# snullv2.net
KiCad netlist of a schematic drawn in EAGLE
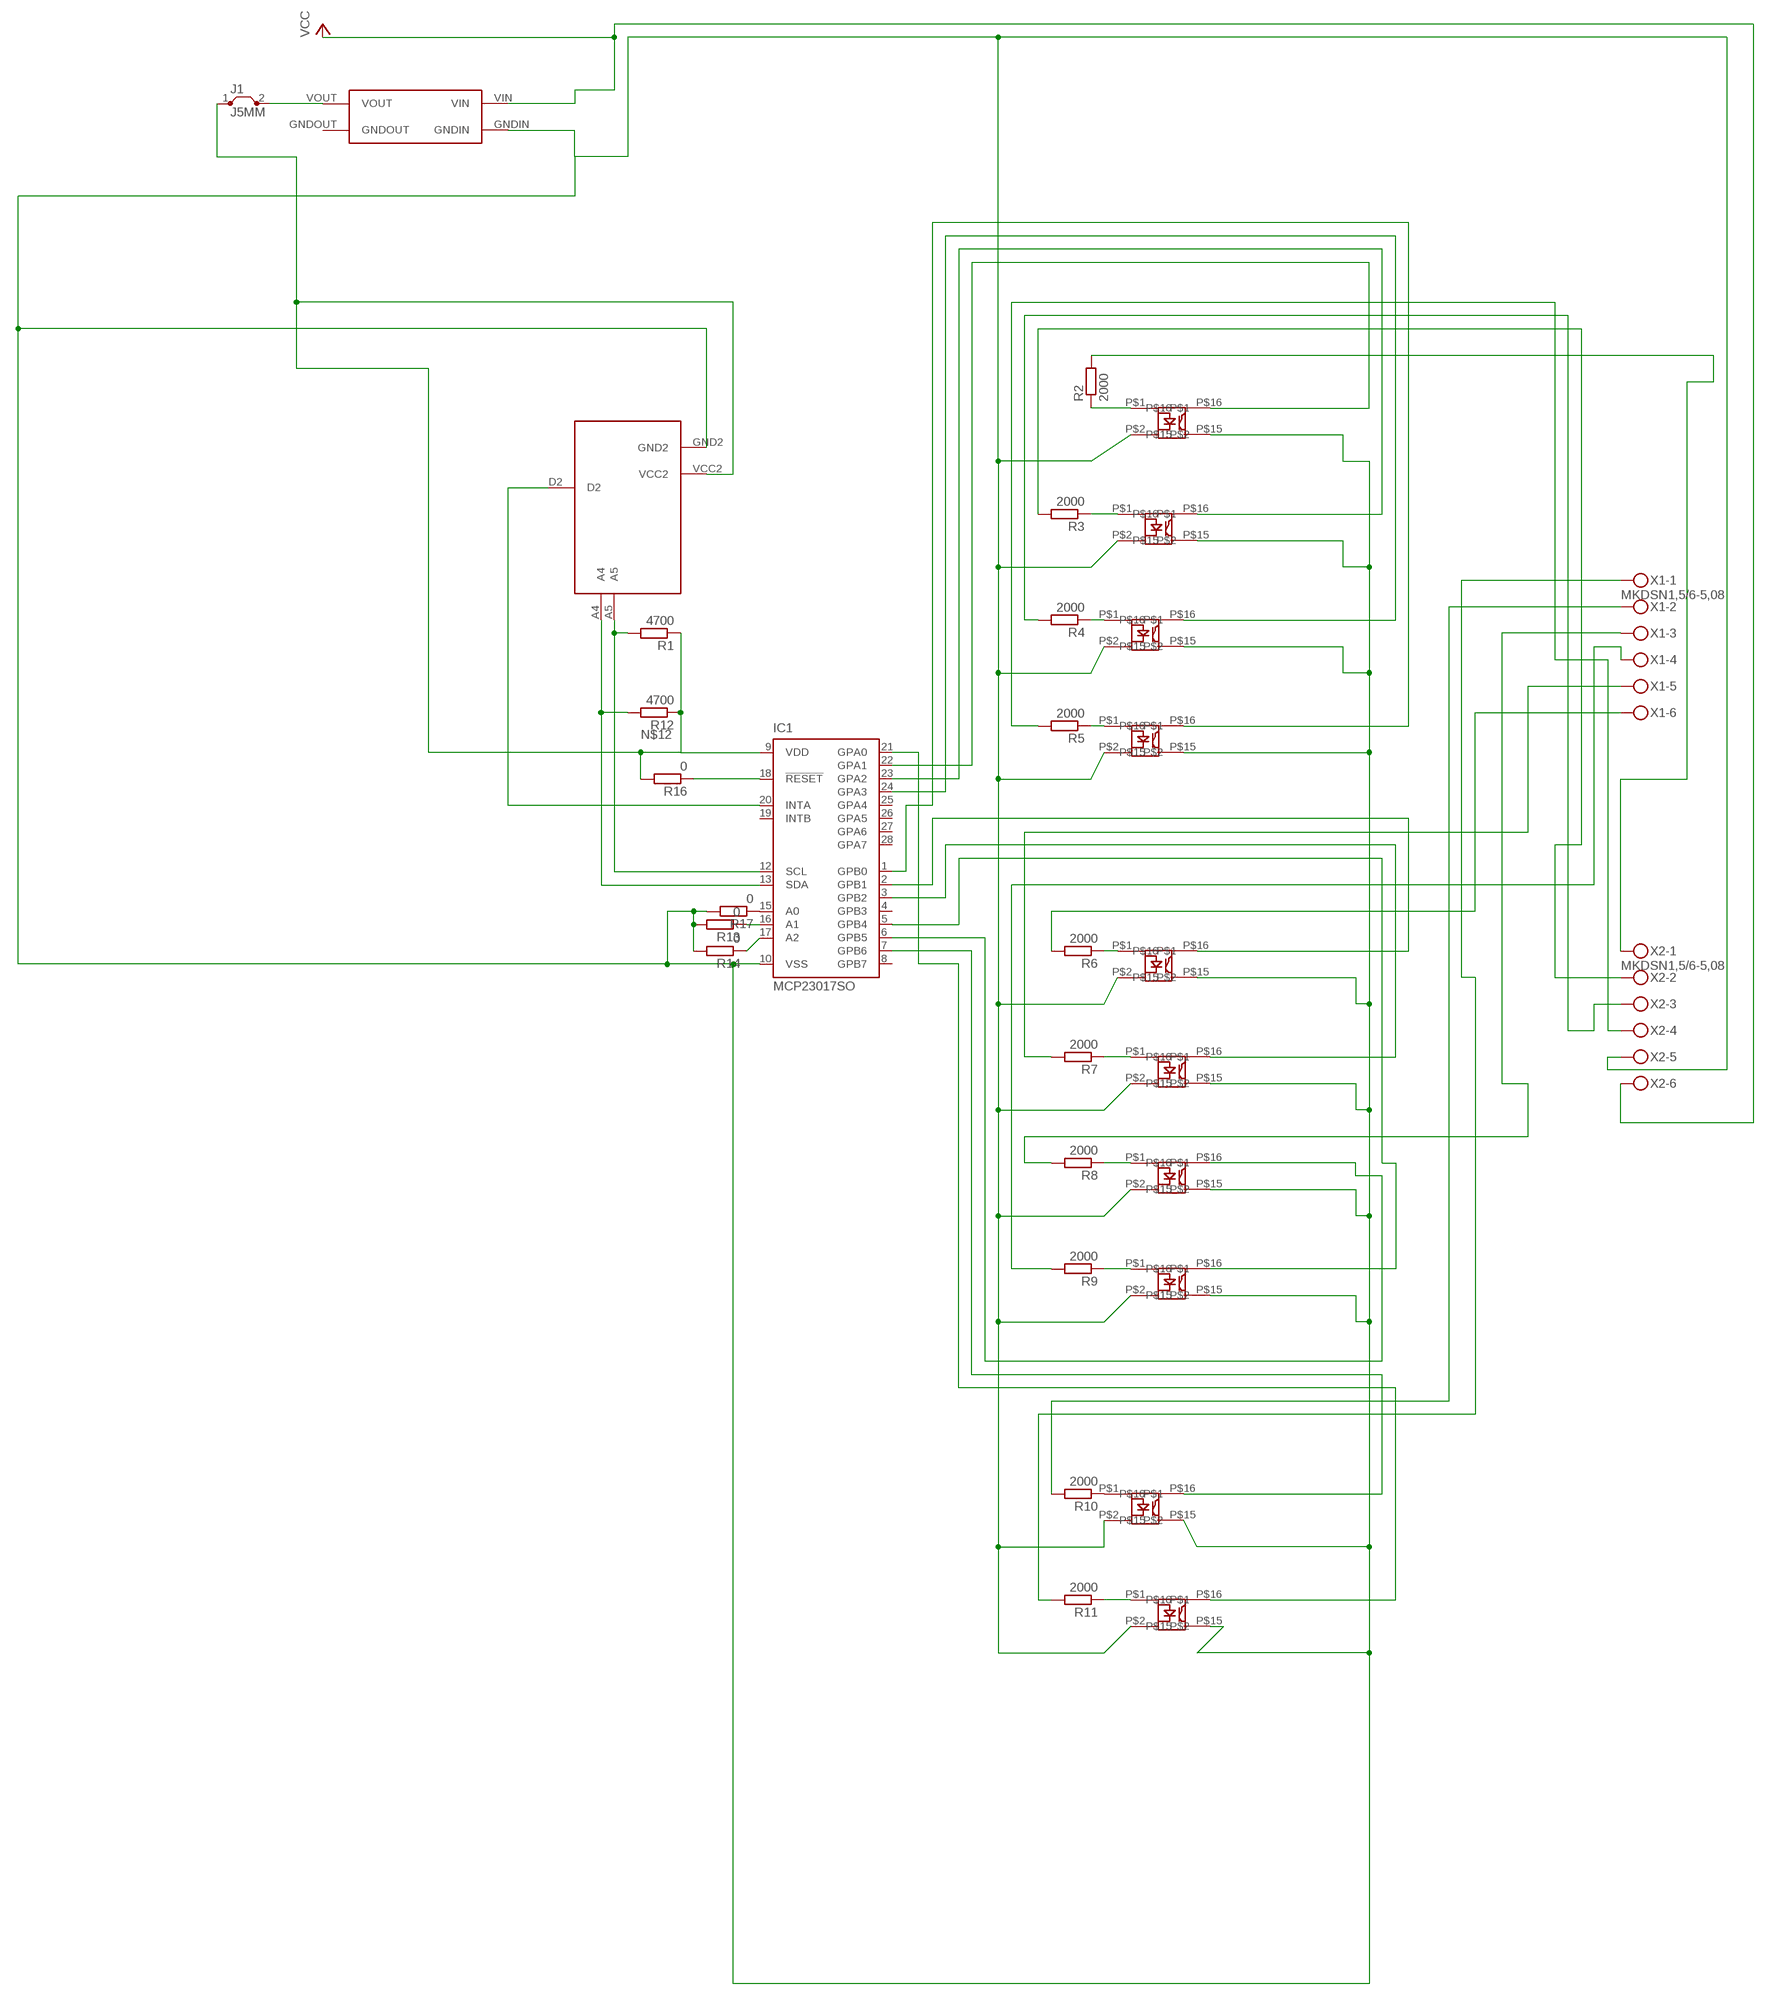
[diagram p0: schematic, sheet 1]

(export (version "E")
  (design (tool "Eeschema 10.0.6"))
  (components
    (comp (ref "IC1")
      (value "MCP23017SO")
      (footprint "eagle-import:SO28W")
      (fields (field (name "MF") "MICROCHIP") (field (name "MPN") "MCP23017-E/SO"))
      (libsource (lib "eagle-import") (part "MCP23017SO"))
    )
    (comp (ref "J1")
      (value "J5MM")
      (footprint "eagle-import:05")
      (libsource (lib "eagle-import") (part "J5MM"))
    )
    (comp (ref "R1")
      (value "4700")
      (footprint "eagle-import:R0805")
      (libsource (lib "eagle-import") (part "R-EU_R0805"))
    )
    (comp (ref "R2")
      (value "2000")
      (footprint "eagle-import:R0805")
      (libsource (lib "eagle-import") (part "R-EU_R0805"))
    )
    (comp (ref "R3")
      (value "2000")
      (footprint "eagle-import:R0805")
      (libsource (lib "eagle-import") (part "R-EU_R0805"))
    )
    (comp (ref "R4")
      (value "2000")
      (footprint "eagle-import:R0805")
      (libsource (lib "eagle-import") (part "R-EU_R0805"))
    )
    (comp (ref "R5")
      (value "2000")
      (footprint "eagle-import:R0805")
      (libsource (lib "eagle-import") (part "R-EU_R0805"))
    )
    (comp (ref "R6")
      (value "2000")
      (footprint "eagle-import:R0805")
      (libsource (lib "eagle-import") (part "R-EU_R0805"))
    )
    (comp (ref "R7")
      (value "2000")
      (footprint "eagle-import:R0805")
      (libsource (lib "eagle-import") (part "R-EU_R0805"))
    )
    (comp (ref "R8")
      (value "2000")
      (footprint "eagle-import:R0805")
      (libsource (lib "eagle-import") (part "R-EU_R0805"))
    )
    (comp (ref "R9")
      (value "2000")
      (footprint "eagle-import:R0805")
      (libsource (lib "eagle-import") (part "R-EU_R0805"))
    )
    (comp (ref "R10")
      (value "2000")
      (footprint "eagle-import:R0805")
      (libsource (lib "eagle-import") (part "R-EU_R0805"))
    )
    (comp (ref "R11")
      (value "2000")
      (footprint "eagle-import:R0805")
      (libsource (lib "eagle-import") (part "R-EU_R0805"))
    )
    (comp (ref "R12")
      (value "4700")
      (footprint "eagle-import:R0805")
      (libsource (lib "eagle-import") (part "R-EU_R0805"))
    )
    (comp (ref "R13")
      (value "0")
      (footprint "eagle-import:R0805")
      (libsource (lib "eagle-import") (part "R-EU_R0805"))
    )
    (comp (ref "R14")
      (value "0")
      (footprint "eagle-import:R0805")
      (libsource (lib "eagle-import") (part "R-EU_R0805"))
    )
    (comp (ref "R16")
      (value "0")
      (footprint "eagle-import:R0805")
      (libsource (lib "eagle-import") (part "R-EU_R0805"))
    )
    (comp (ref "R17")
      (value "0")
      (footprint "eagle-import:R0805")
      (libsource (lib "eagle-import") (part "R-EU_R0805"))
    )
    (comp (ref "U$1")
      (value "ARDUINOPROMINIREDUCED")
      (footprint "eagle-import:ARDUINOPROMINIREDUCED")
      (libsource (lib "eagle-import") (part "ARDUINOPROMINIREDUCED"))
    )
    (comp (ref "U$3")
      (value "OPTO1CHAN")
      (footprint "eagle-import:OPTO1CHAN")
      (libsource (lib "eagle-import") (part "OPTO1CHAN"))
    )
    (comp (ref "U$4")
      (value "OPTO1CHAN")
      (footprint "eagle-import:OPTO1CHAN")
      (libsource (lib "eagle-import") (part "OPTO1CHAN"))
    )
    (comp (ref "U$5")
      (value "VREGMODULE")
      (footprint "eagle-import:VREGMODULE")
      (libsource (lib "eagle-import") (part "VREGMODULE"))
    )
    (comp (ref "U$6")
      (value "OPTO1CHAN")
      (footprint "eagle-import:OPTO1CHAN")
      (libsource (lib "eagle-import") (part "OPTO1CHAN"))
    )
    (comp (ref "U$7")
      (value "OPTO1CHAN")
      (footprint "eagle-import:OPTO1CHAN")
      (libsource (lib "eagle-import") (part "OPTO1CHAN"))
    )
    (comp (ref "U$8")
      (value "OPTO1CHAN")
      (footprint "eagle-import:OPTO1CHAN")
      (libsource (lib "eagle-import") (part "OPTO1CHAN"))
    )
    (comp (ref "U$9")
      (value "OPTO1CHAN")
      (footprint "eagle-import:OPTO1CHAN")
      (libsource (lib "eagle-import") (part "OPTO1CHAN"))
    )
    (comp (ref "U$10")
      (value "OPTO1CHAN")
      (footprint "eagle-import:OPTO1CHAN")
      (libsource (lib "eagle-import") (part "OPTO1CHAN"))
    )
    (comp (ref "U$11")
      (value "OPTO1CHAN")
      (footprint "eagle-import:OPTO1CHAN")
      (libsource (lib "eagle-import") (part "OPTO1CHAN"))
    )
    (comp (ref "U$12")
      (value "OPTO1CHAN")
      (footprint "eagle-import:OPTO1CHAN")
      (libsource (lib "eagle-import") (part "OPTO1CHAN"))
    )
    (comp (ref "U$13")
      (value "OPTO1CHAN")
      (footprint "eagle-import:OPTO1CHAN")
      (libsource (lib "eagle-import") (part "OPTO1CHAN"))
    )
    (comp (ref "X1")
      (value "MKDSN1,5/6-5,08")
      (footprint "eagle-import:MKDSN1,5_6-5,08")
      (libsource (lib "eagle-import") (part "MKDSN1,5/6-5,08"))
    )
    (comp (ref "X2")
      (value "MKDSN1,5/6-5,08")
      (footprint "eagle-import:MKDSN1,5_6-5,08")
      (libsource (lib "eagle-import") (part "MKDSN1,5/6-5,08"))
    )
  )
  (nets
    (net (code "1") (name "/N$12") (class "Default")
      (node (ref "IC1") (pin "9") (pinfunction "VDD_9") (pintype "power_in"))
      (node (ref "J1") (pin "1") (pinfunction "1_1") (pintype "passive"))
      (node (ref "R1") (pin "1") (pinfunction "1_1") (pintype "passive"))
      (node (ref "R12") (pin "1") (pinfunction "1_1") (pintype "passive"))
      (node (ref "R16") (pin "2") (pinfunction "2_2") (pintype "passive"))
      (node (ref "U$1") (pin "VCC2") (pinfunction "VCC2_VCC2") (pintype "bidirectional"))
    )
    (net (code "2") (name "Net-(IC1-A0)") (class "Default")
      (node (ref "IC1") (pin "15") (pinfunction "A0_15") (pintype "input"))
      (node (ref "R17") (pin "1") (pinfunction "1_1") (pintype "passive"))
    )
    (net (code "3") (name "Net-(IC1-A1)") (class "Default")
      (node (ref "IC1") (pin "16") (pinfunction "A1_16") (pintype "input"))
      (node (ref "R13") (pin "1") (pinfunction "1_1") (pintype "passive"))
    )
    (net (code "4") (name "Net-(IC1-A2)") (class "Default")
      (node (ref "IC1") (pin "17") (pinfunction "A2_17") (pintype "input"))
      (node (ref "R14") (pin "1") (pinfunction "1_1") (pintype "passive"))
    )
    (net (code "5") (name "Net-(IC1-GPA0)") (class "Default")
      (node (ref "IC1") (pin "21") (pinfunction "GPA0_21") (pintype "bidirectional"))
      (node (ref "U$13") (pin "P$16") (pinfunction "P$16_P$16") (pintype "bidirectional"))
    )
    (net (code "6") (name "Net-(IC1-GPA1)") (class "Default")
      (node (ref "IC1") (pin "22") (pinfunction "GPA1_22") (pintype "bidirectional"))
      (node (ref "U$3") (pin "P$16") (pinfunction "P$16_P$16") (pintype "bidirectional"))
    )
    (net (code "7") (name "Net-(IC1-GPA2)") (class "Default")
      (node (ref "IC1") (pin "23") (pinfunction "GPA2_23") (pintype "bidirectional"))
      (node (ref "U$4") (pin "P$16") (pinfunction "P$16_P$16") (pintype "bidirectional"))
    )
    (net (code "8") (name "Net-(IC1-GPA3)") (class "Default")
      (node (ref "IC1") (pin "24") (pinfunction "GPA3_24") (pintype "bidirectional"))
      (node (ref "U$6") (pin "P$16") (pinfunction "P$16_P$16") (pintype "bidirectional"))
    )
    (net (code "9") (name "Net-(IC1-GPB0)") (class "Default")
      (node (ref "IC1") (pin "1") (pinfunction "GPB0_1") (pintype "bidirectional"))
      (node (ref "U$7") (pin "P$16") (pinfunction "P$16_P$16") (pintype "bidirectional"))
    )
    (net (code "10") (name "Net-(IC1-GPB1)") (class "Default")
      (node (ref "IC1") (pin "2") (pinfunction "GPB1_2") (pintype "bidirectional"))
      (node (ref "U$8") (pin "P$16") (pinfunction "P$16_P$16") (pintype "bidirectional"))
    )
    (net (code "11") (name "Net-(IC1-GPB2)") (class "Default")
      (node (ref "IC1") (pin "3") (pinfunction "GPB2_3") (pintype "bidirectional"))
      (node (ref "U$9") (pin "P$16") (pinfunction "P$16_P$16") (pintype "bidirectional"))
    )
    (net (code "12") (name "Net-(IC1-GPB4)") (class "Default")
      (node (ref "IC1") (pin "5") (pinfunction "GPB4_5") (pintype "bidirectional"))
      (node (ref "U$11") (pin "P$16") (pinfunction "P$16_P$16") (pintype "bidirectional"))
    )
    (net (code "13") (name "Net-(IC1-GPB5)") (class "Default")
      (node (ref "IC1") (pin "6") (pinfunction "GPB5_6") (pintype "bidirectional"))
      (node (ref "U$10") (pin "P$16") (pinfunction "P$16_P$16") (pintype "bidirectional"))
    )
    (net (code "14") (name "Net-(IC1-GPB6)") (class "Default")
      (node (ref "IC1") (pin "7") (pinfunction "GPB6_7") (pintype "bidirectional"))
      (node (ref "U$12") (pin "P$16") (pinfunction "P$16_P$16") (pintype "bidirectional"))
    )
    (net (code "15") (name "Net-(IC1-INTA)") (class "Default")
      (node (ref "IC1") (pin "20") (pinfunction "INTA_20") (pintype "output"))
      (node (ref "U$1") (pin "D2") (pinfunction "D2_D2") (pintype "bidirectional"))
    )
    (net (code "16") (name "Net-(IC1-SCL)") (class "Default")
      (node (ref "IC1") (pin "12") (pinfunction "SCL_12") (pintype "input"))
      (node (ref "R1") (pin "2") (pinfunction "2_2") (pintype "passive"))
      (node (ref "U$1") (pin "A5") (pinfunction "A5_A5") (pintype "bidirectional"))
    )
    (net (code "17") (name "Net-(IC1-SDA)") (class "Default")
      (node (ref "IC1") (pin "13") (pinfunction "SDA_13") (pintype "bidirectional"))
      (node (ref "R12") (pin "2") (pinfunction "2_2") (pintype "passive"))
      (node (ref "U$1") (pin "A4") (pinfunction "A4_A4") (pintype "bidirectional"))
    )
    (net (code "18") (name "Net-(IC1-VSS)") (class "Default")
      (node (ref "IC1") (pin "10") (pinfunction "VSS_10") (pintype "power_in"))
      (node (ref "R13") (pin "2") (pinfunction "2_2") (pintype "passive"))
      (node (ref "R14") (pin "2") (pinfunction "2_2") (pintype "passive"))
      (node (ref "R17") (pin "2") (pinfunction "2_2") (pintype "passive"))
      (node (ref "U$1") (pin "GND2") (pinfunction "GND2_GND2") (pintype "bidirectional"))
      (node (ref "U$10") (pin "P$15") (pinfunction "P$15_P$15") (pintype "bidirectional"))
      (node (ref "U$10") (pin "P$2") (pinfunction "P$2_P$2") (pintype "bidirectional"))
      (node (ref "U$11") (pin "P$15") (pinfunction "P$15_P$15") (pintype "bidirectional"))
      (node (ref "U$11") (pin "P$2") (pinfunction "P$2_P$2") (pintype "bidirectional"))
      (node (ref "U$12") (pin "P$15") (pinfunction "P$15_P$15") (pintype "bidirectional"))
      (node (ref "U$12") (pin "P$2") (pinfunction "P$2_P$2") (pintype "bidirectional"))
      (node (ref "U$13") (pin "P$15") (pinfunction "P$15_P$15") (pintype "bidirectional"))
      (node (ref "U$13") (pin "P$2") (pinfunction "P$2_P$2") (pintype "bidirectional"))
      (node (ref "U$3") (pin "P$15") (pinfunction "P$15_P$15") (pintype "bidirectional"))
      (node (ref "U$3") (pin "P$2") (pinfunction "P$2_P$2") (pintype "bidirectional"))
      (node (ref "U$4") (pin "P$15") (pinfunction "P$15_P$15") (pintype "bidirectional"))
      (node (ref "U$4") (pin "P$2") (pinfunction "P$2_P$2") (pintype "bidirectional"))
      (node (ref "U$5") (pin "GNDIN") (pinfunction "GNDIN_GNDIN") (pintype "bidirectional"))
      (node (ref "U$6") (pin "P$15") (pinfunction "P$15_P$15") (pintype "bidirectional"))
      (node (ref "U$6") (pin "P$2") (pinfunction "P$2_P$2") (pintype "bidirectional"))
      (node (ref "U$7") (pin "P$15") (pinfunction "P$15_P$15") (pintype "bidirectional"))
      (node (ref "U$7") (pin "P$2") (pinfunction "P$2_P$2") (pintype "bidirectional"))
      (node (ref "U$8") (pin "P$15") (pinfunction "P$15_P$15") (pintype "bidirectional"))
      (node (ref "U$8") (pin "P$2") (pinfunction "P$2_P$2") (pintype "bidirectional"))
      (node (ref "U$9") (pin "P$15") (pinfunction "P$15_P$15") (pintype "bidirectional"))
      (node (ref "U$9") (pin "P$2") (pinfunction "P$2_P$2") (pintype "bidirectional"))
      (node (ref "X2") (pin "5") (pinfunction "KL_5") (pintype "passive"))
    )
    (net (code "19") (name "Net-(IC1-~{RESET})") (class "Default")
      (node (ref "IC1") (pin "18") (pinfunction "~{RESET}_18") (pintype "input"))
      (node (ref "R16") (pin "1") (pinfunction "1_1") (pintype "passive"))
    )
    (net (code "20") (name "Net-(J1-Pad2)") (class "Default")
      (node (ref "J1") (pin "2") (pinfunction "2_2") (pintype "passive"))
      (node (ref "U$5") (pin "VOUT") (pinfunction "VOUT_VOUT") (pintype "bidirectional"))
    )
    (net (code "21") (name "Net-(R2-Pad1)") (class "Default")
      (node (ref "R2") (pin "1") (pinfunction "1_1") (pintype "passive"))
      (node (ref "U$3") (pin "P$1") (pinfunction "P$1_P$1") (pintype "bidirectional"))
    )
    (net (code "22") (name "Net-(R3-Pad1)") (class "Default")
      (node (ref "R3") (pin "1") (pinfunction "1_1") (pintype "passive"))
      (node (ref "U$4") (pin "P$1") (pinfunction "P$1_P$1") (pintype "bidirectional"))
    )
    (net (code "23") (name "Net-(R4-Pad1)") (class "Default")
      (node (ref "R4") (pin "1") (pinfunction "1_1") (pintype "passive"))
      (node (ref "U$6") (pin "P$1") (pinfunction "P$1_P$1") (pintype "bidirectional"))
    )
    (net (code "24") (name "Net-(R5-Pad1)") (class "Default")
      (node (ref "R5") (pin "1") (pinfunction "1_1") (pintype "passive"))
      (node (ref "U$7") (pin "P$1") (pinfunction "P$1_P$1") (pintype "bidirectional"))
    )
    (net (code "25") (name "Net-(R6-Pad1)") (class "Default")
      (node (ref "R6") (pin "1") (pinfunction "1_1") (pintype "passive"))
      (node (ref "U$8") (pin "P$1") (pinfunction "P$1_P$1") (pintype "bidirectional"))
    )
    (net (code "26") (name "Net-(R7-Pad1)") (class "Default")
      (node (ref "R7") (pin "1") (pinfunction "1_1") (pintype "passive"))
      (node (ref "U$9") (pin "P$1") (pinfunction "P$1_P$1") (pintype "bidirectional"))
    )
    (net (code "27") (name "Net-(R8-Pad1)") (class "Default")
      (node (ref "R8") (pin "1") (pinfunction "1_1") (pintype "passive"))
      (node (ref "U$10") (pin "P$1") (pinfunction "P$1_P$1") (pintype "bidirectional"))
    )
    (net (code "28") (name "Net-(R9-Pad1)") (class "Default")
      (node (ref "R9") (pin "1") (pinfunction "1_1") (pintype "passive"))
      (node (ref "U$11") (pin "P$1") (pinfunction "P$1_P$1") (pintype "bidirectional"))
    )
    (net (code "29") (name "Net-(R10-Pad1)") (class "Default")
      (node (ref "R10") (pin "1") (pinfunction "1_1") (pintype "passive"))
      (node (ref "U$12") (pin "P$1") (pinfunction "P$1_P$1") (pintype "bidirectional"))
    )
    (net (code "30") (name "Net-(R11-Pad1)") (class "Default")
      (node (ref "R11") (pin "1") (pinfunction "1_1") (pintype "passive"))
      (node (ref "U$13") (pin "P$1") (pinfunction "P$1_P$1") (pintype "bidirectional"))
    )
    (net (code "31") (name "Net-(X1A-KL)") (class "Default")
      (node (ref "R11") (pin "2") (pinfunction "2_2") (pintype "passive"))
      (node (ref "X1") (pin "1") (pinfunction "KL_1") (pintype "passive"))
    )
    (net (code "32") (name "Net-(X1B-KL)") (class "Default")
      (node (ref "R10") (pin "2") (pinfunction "2_2") (pintype "passive"))
      (node (ref "X1") (pin "2") (pinfunction "KL_2") (pintype "passive"))
    )
    (net (code "33") (name "Net-(X1C-KL)") (class "Default")
      (node (ref "R8") (pin "2") (pinfunction "2_2") (pintype "passive"))
      (node (ref "X1") (pin "3") (pinfunction "KL_3") (pintype "passive"))
    )
    (net (code "34") (name "Net-(X1D-KL)") (class "Default")
      (node (ref "R9") (pin "2") (pinfunction "2_2") (pintype "passive"))
      (node (ref "X1") (pin "4") (pinfunction "KL_4") (pintype "passive"))
    )
    (net (code "35") (name "Net-(X1E-KL)") (class "Default")
      (node (ref "R7") (pin "2") (pinfunction "2_2") (pintype "passive"))
      (node (ref "X1") (pin "5") (pinfunction "KL_5") (pintype "passive"))
    )
    (net (code "36") (name "Net-(X1F-KL)") (class "Default")
      (node (ref "R6") (pin "2") (pinfunction "2_2") (pintype "passive"))
      (node (ref "X1") (pin "6") (pinfunction "KL_6") (pintype "passive"))
    )
    (net (code "37") (name "Net-(X2A-KL)") (class "Default")
      (node (ref "R2") (pin "2") (pinfunction "2_2") (pintype "passive"))
      (node (ref "X2") (pin "1") (pinfunction "KL_1") (pintype "passive"))
    )
    (net (code "38") (name "Net-(X2B-KL)") (class "Default")
      (node (ref "R3") (pin "2") (pinfunction "2_2") (pintype "passive"))
      (node (ref "X2") (pin "2") (pinfunction "KL_2") (pintype "passive"))
    )
    (net (code "39") (name "Net-(X2C-KL)") (class "Default")
      (node (ref "R4") (pin "2") (pinfunction "2_2") (pintype "passive"))
      (node (ref "X2") (pin "3") (pinfunction "KL_3") (pintype "passive"))
    )
    (net (code "40") (name "Net-(X2D-KL)") (class "Default")
      (node (ref "R5") (pin "2") (pinfunction "2_2") (pintype "passive"))
      (node (ref "X2") (pin "4") (pinfunction "KL_4") (pintype "passive"))
    )
    (net (code "41") (name "VCC") (class "Default")
      (node (ref "U$5") (pin "VIN") (pinfunction "VIN_VIN") (pintype "bidirectional"))
      (node (ref "X2") (pin "6") (pinfunction "KL_6") (pintype "passive"))
    )
    (net (code "42") (name "unconnected-(IC1-GPA4-Pad25)") (class "Default")
      (node (ref "IC1") (pin "25") (pinfunction "GPA4_25") (pintype "bidirectional"))
    )
    (net (code "43") (name "unconnected-(IC1-GPA5-Pad26)") (class "Default")
      (node (ref "IC1") (pin "26") (pinfunction "GPA5_26") (pintype "bidirectional"))
    )
    (net (code "44") (name "unconnected-(IC1-GPA6-Pad27)") (class "Default")
      (node (ref "IC1") (pin "27") (pinfunction "GPA6_27") (pintype "bidirectional"))
    )
    (net (code "45") (name "unconnected-(IC1-GPA7-Pad28)") (class "Default")
      (node (ref "IC1") (pin "28") (pinfunction "GPA7_28") (pintype "bidirectional"))
    )
    (net (code "46") (name "unconnected-(IC1-GPB3-Pad4)") (class "Default")
      (node (ref "IC1") (pin "4") (pinfunction "GPB3_4") (pintype "bidirectional"))
    )
    (net (code "47") (name "unconnected-(IC1-GPB7-Pad8)") (class "Default")
      (node (ref "IC1") (pin "8") (pinfunction "GPB7_8") (pintype "bidirectional"))
    )
    (net (code "48") (name "unconnected-(IC1-INTB-Pad19)") (class "Default")
      (node (ref "IC1") (pin "19") (pinfunction "INTB_19") (pintype "output"))
    )
    (net (code "49") (name "unconnected-(U$5-PadGNDOUT)") (class "Default")
      (node (ref "U$5") (pin "GNDOUT") (pinfunction "GNDOUT_GNDOUT") (pintype "bidirectional"))
    )
  )
)
